# 01-PCIe.net
KiCad netlist of a schematic drawn in Altium Designer
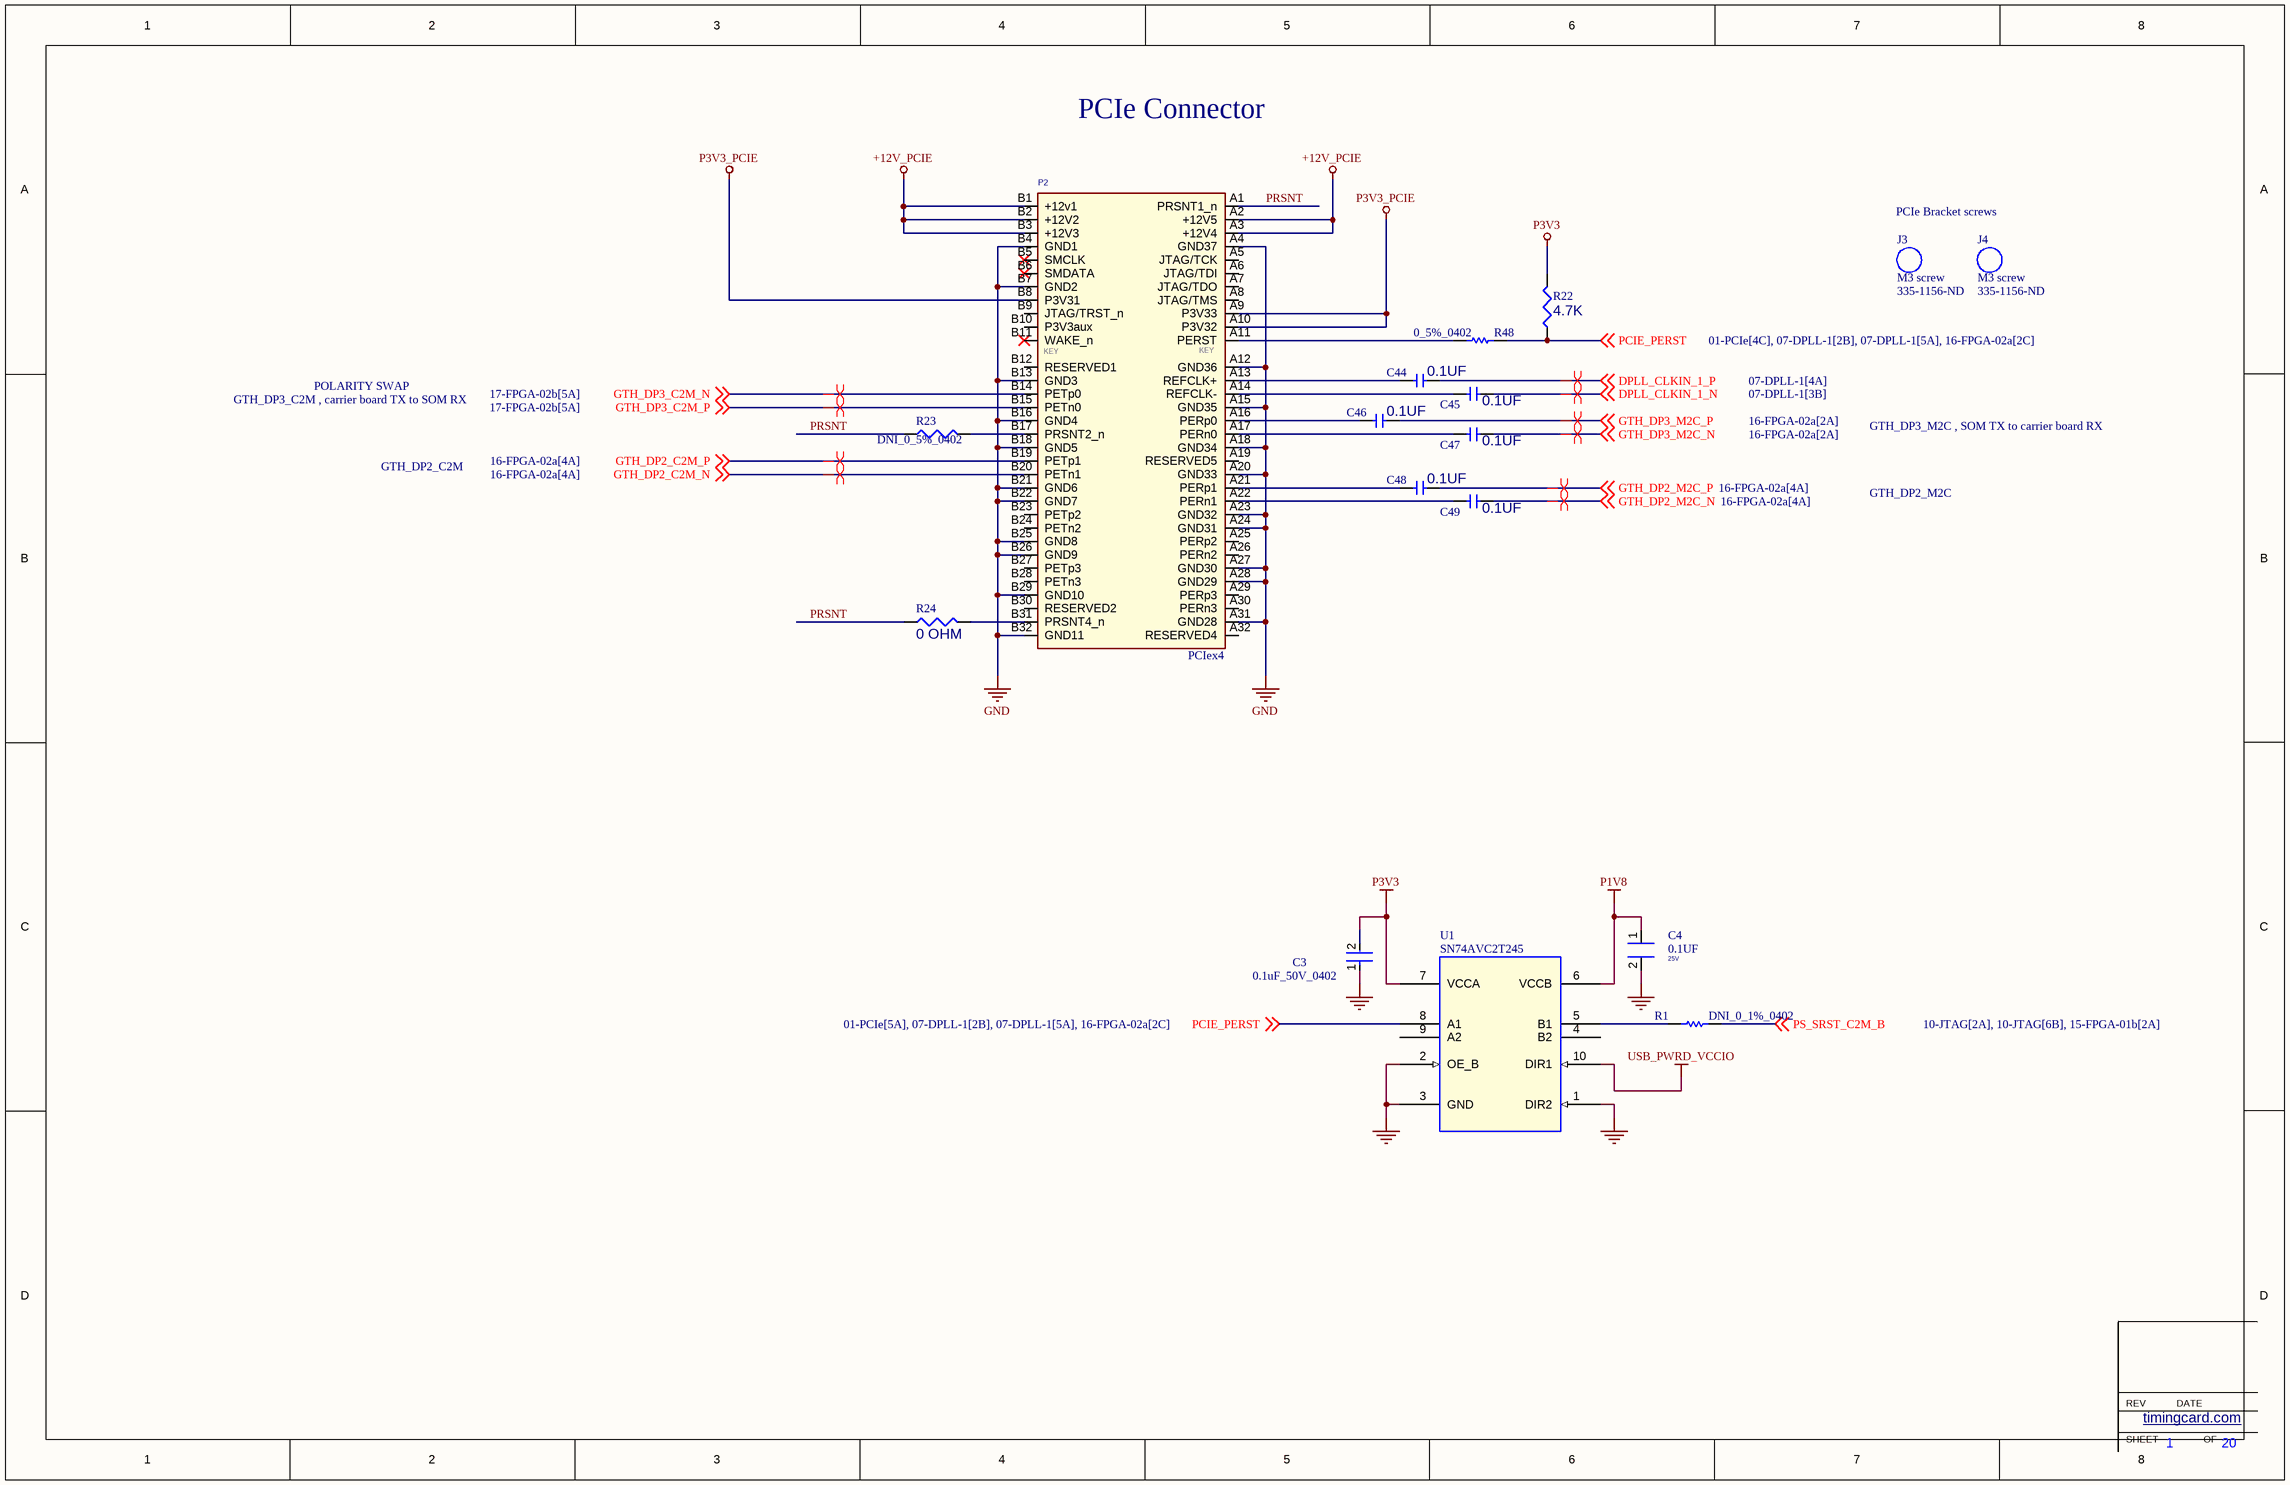
[diagram p0: 01-PCIe.SchDoc]

(export (version "E")
  (design (tool "Eeschema 10.0.6"))
  (components
    (comp (ref "C3")
      (value "0.1uF_50V_0402")
      (footprint "FP-C1005-050-0_05-IPC_C")
      (description "Multilayer Ceramic Capacitors 100nF ±10% 50V X7R SMD 0402")
      (fields (field (name "VOLTAGE") "50V") (field (name "TOLERANCE") "10%"))
      (libsource (lib "Altium Content Vault") (part "b4654b650e69147ec39a6b967a45e02"))
    )
    (comp (ref "C4")
      (value "0.1UF")
      (footprint "CAPC100X50X55")
      (description "Cap Cer 100nF 10% 25V X5R 0402")
      (fields
        (field (name "VOLTAGE") "25V")
        (field (name "MANUFACTURER") "TAIYO YUDEN")
        (field (name "AGILE PART NUMBER") "CAP-00068-01")
        (field (name "OWNER") "4001")
      )
      (libsource (lib "*") (part "CAP_NP"))
    )
    (comp (ref "C44")
      (value "0.1UF")
      (footprint "CAPC1005X06N")
      (description "CAP, CER, 0.1UF, 50V, 10%, X7R, AEC-Q200, 0402")
      (fields
        (field (name "MFG PART NUM") "CGA2B3X7R1H104K050BB")
        (field (name "VALENTIUM PART NUM") "<VALENTIUM>")
      )
      (libsource (lib "Capacitors") (part "CAP_0402_0.1UF_50V"))
    )
    (comp (ref "C45")
      (value "0.1UF")
      (footprint "CAPC1005X06N")
      (description "CAP, CER, 0.1UF, 50V, 10%, X7R, AEC-Q200, 0402")
      (fields
        (field (name "MFG PART NUM") "CGA2B3X7R1H104K050BB")
        (field (name "VALENTIUM PART NUM") "<VALENTIUM>")
      )
      (libsource (lib "Capacitors") (part "CAP_0402_0.1UF_50V"))
    )
    (comp (ref "C46")
      (value "0.1UF")
      (footprint "CAPC1005X06N")
      (description "CAP, CER, 0.1UF, 50V, 10%, X7R, AEC-Q200, 0402")
      (fields
        (field (name "MFG PART NUM") "CGA2B3X7R1H104K050BB")
        (field (name "VALENTIUM PART NUM") "<VALENTIUM>")
      )
      (libsource (lib "Capacitors") (part "CAP_0402_0.1UF_50V"))
    )
    (comp (ref "C47")
      (value "0.1UF")
      (footprint "CAPC1005X06N")
      (description "CAP, CER, 0.1UF, 50V, 10%, X7R, AEC-Q200, 0402")
      (fields
        (field (name "MFG PART NUM") "CGA2B3X7R1H104K050BB")
        (field (name "VALENTIUM PART NUM") "<VALENTIUM>")
      )
      (libsource (lib "Capacitors") (part "CAP_0402_0.1UF_50V"))
    )
    (comp (ref "C48")
      (value "0.1UF")
      (footprint "CAPC1005X06N")
      (description "CAP, CER, 0.1UF, 50V, 10%, X7R, AEC-Q200, 0402")
      (fields
        (field (name "MFG PART NUM") "CGA2B3X7R1H104K050BB")
        (field (name "VALENTIUM PART NUM") "<VALENTIUM>")
      )
      (libsource (lib "Capacitors") (part "CAP_0402_0.1UF_50V"))
    )
    (comp (ref "C49")
      (value "0.1UF")
      (footprint "CAPC1005X06N")
      (description "CAP, CER, 0.1UF, 50V, 10%, X7R, AEC-Q200, 0402")
      (fields
        (field (name "MFG PART NUM") "CGA2B3X7R1H104K050BB")
        (field (name "VALENTIUM PART NUM") "<VALENTIUM>")
      )
      (libsource (lib "Capacitors") (part "CAP_0402_0.1UF_50V"))
    )
    (comp (ref "J3")
      (value "M3 screw")
      (fields (field (name "SUPPLIER PART NUMBER 1") "335-1156-ND"))
      (libsource (lib "FPGA_CONN") (part "M3 screw"))
    )
    (comp (ref "J4")
      (value "M3 screw")
      (fields (field (name "SUPPLIER PART NUMBER 1") "335-1156-ND"))
      (libsource (lib "FPGA_CONN") (part "M3 screw"))
    )
    (comp (ref "P2")
      (value "PCIex4")
      (footprint "PCIE_4LANE_EDGE")
      (description "PCIE x4 Edge Connector,OrCAD Symbol,NC")
      (fields (field (name "PART NUMBER") "451") (field (name "MANUFACTURER") "NA"))
      (libsource (lib "Connectors") (part "PCIex4"))
    )
    (comp (ref "R1")
      (value "DNI_0_1%_0402")
      (footprint "RESC1005X40X25LL05T05")
      (description "Chip Resistor, 0 Ohm, 0.1 W, -55 to 155 degC, 0402 (1005 Metric), RoHS, Tape and Reel")
      (fields (field (name "MANUFACTURER") "Panasonic") (field (name "TOLERANCE") "5%"))
      (libsource (lib "Altium Content Vault") (part "RES-2"))
    )
    (comp (ref "R22")
      (value "4.7K")
      (footprint "RESC1608X50N")
      (description "RES, 4.7K, 1%, 1/10W, TF, 0603")
      (fields (field (name "MFG PART NUM") "ERJ-3EKF4701V") (field (name "VELENTIUM PART NUM") "<VELENTIUM>"))
      (libsource (lib "Resistors") (part "RES_0603_4.7K"))
    )
    (comp (ref "R23")
      (value "DNI_0_5%_0402")
      (footprint "RESC1005X04N")
      (description "RES, 0. OHM, 1%, 1/16W, TF, AEC-Q200, 0402")
      (fields (field (name "MFG PART NUM") "ERJ-2GE0R00X") (field (name "VELENTIUM PART NUM") "<VELENTIUM>"))
      (libsource (lib "Resistors") (part "RES_0402_0"))
    )
    (comp (ref "R24")
      (value "0 OHM")
      (footprint "RESC1005X04N")
      (description "RES, 0. OHM, 1%, 1/16W, TF, AEC-Q200, 0402")
      (fields (field (name "MFG PART NUM") "ERJ-2GE0R00X") (field (name "VELENTIUM PART NUM") "<VELENTIUM>"))
      (libsource (lib "Resistors") (part "RES_0402_0"))
    )
    (comp (ref "R48")
      (value "0_5%_0402")
      (footprint "RESC1005X40X25LL10T10")
      (fields (field (name "MANUFACTURER") "KOA Speer") (field (name "PART NUMBER") "RK73Z1ETTP"))
      (libsource (lib "Altium Content Vault") (part "RES"))
    )
    (comp (ref "U1")
      (value "SN74AVC2T245")
      (footprint "QFN40P140X180X55-10")
      (description "IC Lvl Trans 2-Bit Bidir 500Mbps 1.2-3.6V 50mA UQFN-10")
      (fields
        (field (name "MANUFACTURER") "TEXAS INSTRUMENTS")
        (field (name "AGILE PART NUMBER") "ICS-00048-01")
      )
      (libsource (lib "*") (part "SN74AVC2T245"))
    )
  )
  (nets
    (net (code "1") (name "+12V_PCIE") (class "Default")
      (node (ref "P2") (pin "A2") (pinfunction "+12V5_A2") (pintype "passive"))
      (node (ref "P2") (pin "A3") (pinfunction "+12V4_A3") (pintype "passive"))
      (node (ref "P2") (pin "B1") (pinfunction "+12v1_B1") (pintype "power_in"))
      (node (ref "P2") (pin "B2") (pinfunction "+12V2_B2") (pintype "power_in"))
      (node (ref "P2") (pin "B3") (pinfunction "+12V3_B3") (pintype "power_in"))
    )
    (net (code "2") (name "/PRSNT") (class "Default")
      (node (ref "P2") (pin "A1") (pinfunction "PRSNT1_n_A1") (pintype "passive"))
      (node (ref "R23") (pin "1") (pinfunction "1_1") (pintype "passive"))
      (node (ref "R24") (pin "1") (pinfunction "1_1") (pintype "passive"))
    )
    (net (code "3") (name "DPLL_CLKIN_1_N") (class "Default")
      (node (ref "C45") (pin "2") (pinfunction "2_2") (pintype "passive"))
    )
    (net (code "4") (name "DPLL_CLKIN_1_P") (class "Default")
      (node (ref "C44") (pin "2") (pinfunction "2_2") (pintype "passive"))
    )
    (net (code "5") (name "GND") (class "Default")
      (node (ref "C3") (pin "1") (pinfunction "1_1") (pintype "passive"))
      (node (ref "C4") (pin "2") (pinfunction "2_2") (pintype "passive"))
      (node (ref "P2") (pin "A12") (pinfunction "GND36_A12") (pintype "power_in"))
      (node (ref "P2") (pin "A15") (pinfunction "GND35_A15") (pintype "power_in"))
      (node (ref "P2") (pin "A18") (pinfunction "GND34_A18") (pintype "power_in"))
      (node (ref "P2") (pin "A20") (pinfunction "GND33_A20") (pintype "power_in"))
      (node (ref "P2") (pin "A23") (pinfunction "GND32_A23") (pintype "power_in"))
      (node (ref "P2") (pin "A24") (pinfunction "GND31_A24") (pintype "power_in"))
      (node (ref "P2") (pin "A27") (pinfunction "GND30_A27") (pintype "power_in"))
      (node (ref "P2") (pin "A28") (pinfunction "GND29_A28") (pintype "power_in"))
      (node (ref "P2") (pin "A31") (pinfunction "GND28_A31") (pintype "power_in"))
      (node (ref "P2") (pin "A4") (pinfunction "GND37_A4") (pintype "power_in"))
      (node (ref "P2") (pin "B13") (pinfunction "GND3_B13") (pintype "power_in"))
      (node (ref "P2") (pin "B16") (pinfunction "GND4_B16") (pintype "power_in"))
      (node (ref "P2") (pin "B18") (pinfunction "GND5_B18") (pintype "power_in"))
      (node (ref "P2") (pin "B21") (pinfunction "GND6_B21") (pintype "power_in"))
      (node (ref "P2") (pin "B22") (pinfunction "GND7_B22") (pintype "power_in"))
      (node (ref "P2") (pin "B25") (pinfunction "GND8_B25") (pintype "power_in"))
      (node (ref "P2") (pin "B26") (pinfunction "GND9_B26") (pintype "power_in"))
      (node (ref "P2") (pin "B29") (pinfunction "GND10_B29") (pintype "power_in"))
      (node (ref "P2") (pin "B32") (pinfunction "GND11_B32") (pintype "power_in"))
      (node (ref "P2") (pin "B4") (pinfunction "GND1_B4") (pintype "power_in"))
      (node (ref "P2") (pin "B7") (pinfunction "GND2_B7") (pintype "power_in"))
      (node (ref "U1") (pin "1") (pinfunction "DIR2_1") (pintype "input"))
      (node (ref "U1") (pin "2") (pinfunction "OE_B_2") (pintype "input"))
      (node (ref "U1") (pin "3") (pinfunction "GND_3") (pintype "power_in"))
    )
    (net (code "6") (name "GTH_DP2_C2M_N") (class "Default")
      (node (ref "P2") (pin "B20") (pinfunction "PETn1_B20") (pintype "passive"))
    )
    (net (code "7") (name "GTH_DP2_C2M_P") (class "Default")
      (node (ref "P2") (pin "B19") (pinfunction "PETp1_B19") (pintype "passive"))
    )
    (net (code "8") (name "GTH_DP2_M2C_N") (class "Default")
      (node (ref "C49") (pin "2") (pinfunction "2_2") (pintype "passive"))
    )
    (net (code "9") (name "GTH_DP2_M2C_P") (class "Default")
      (node (ref "C48") (pin "2") (pinfunction "2_2") (pintype "passive"))
    )
    (net (code "10") (name "GTH_DP3_C2M_N") (class "Default")
      (node (ref "P2") (pin "B14") (pinfunction "PETp0_B14") (pintype "passive"))
    )
    (net (code "11") (name "GTH_DP3_C2M_P") (class "Default")
      (node (ref "P2") (pin "B15") (pinfunction "PETn0_B15") (pintype "passive"))
    )
    (net (code "12") (name "GTH_DP3_M2C_N") (class "Default")
      (node (ref "C47") (pin "2") (pinfunction "2_2") (pintype "passive"))
    )
    (net (code "13") (name "GTH_DP3_M2C_P") (class "Default")
      (node (ref "C46") (pin "2") (pinfunction "2_2") (pintype "passive"))
    )
    (net (code "14") (name "Net-(P2-PERST)") (class "Default")
      (node (ref "P2") (pin "A11") (pinfunction "PERST_A11") (pintype "passive"))
      (node (ref "R48") (pin "1") (pinfunction "1_1") (pintype "passive"))
    )
    (net (code "15") (name "Net-(P2-PERn0)") (class "Default")
      (node (ref "C47") (pin "1") (pinfunction "1_1") (pintype "passive"))
      (node (ref "P2") (pin "A17") (pinfunction "PERn0_A17") (pintype "passive"))
    )
    (net (code "16") (name "Net-(P2-PERn1)") (class "Default")
      (node (ref "C49") (pin "1") (pinfunction "1_1") (pintype "passive"))
      (node (ref "P2") (pin "A22") (pinfunction "PERn1_A22") (pintype "passive"))
    )
    (net (code "17") (name "Net-(P2-PERp0)") (class "Default")
      (node (ref "C46") (pin "1") (pinfunction "1_1") (pintype "passive"))
      (node (ref "P2") (pin "A16") (pinfunction "PERp0_A16") (pintype "passive"))
    )
    (net (code "18") (name "Net-(P2-PERp1)") (class "Default")
      (node (ref "C48") (pin "1") (pinfunction "1_1") (pintype "passive"))
      (node (ref "P2") (pin "A21") (pinfunction "PERp1_A21") (pintype "passive"))
    )
    (net (code "19") (name "Net-(P2-PRSNT2_n)") (class "Default")
      (node (ref "P2") (pin "B17") (pinfunction "PRSNT2_n_B17") (pintype "passive"))
      (node (ref "R23") (pin "2") (pinfunction "2_2") (pintype "passive"))
    )
    (net (code "20") (name "Net-(P2-PRSNT4_n)") (class "Default")
      (node (ref "P2") (pin "B31") (pinfunction "PRSNT4_n_B31") (pintype "passive"))
      (node (ref "R24") (pin "2") (pinfunction "2_2") (pintype "passive"))
    )
    (net (code "21") (name "Net-(P2-REFCLK+)") (class "Default")
      (node (ref "C44") (pin "1") (pinfunction "1_1") (pintype "passive"))
      (node (ref "P2") (pin "A13") (pinfunction "REFCLK+_A13") (pintype "passive"))
    )
    (net (code "22") (name "Net-(P2-REFCLK-)") (class "Default")
      (node (ref "C45") (pin "1") (pinfunction "1_1") (pintype "passive"))
      (node (ref "P2") (pin "A14") (pinfunction "REFCLK-_A14") (pintype "passive"))
    )
    (net (code "23") (name "Net-(U1-B1)") (class "Default")
      (node (ref "R1") (pin "1") (pinfunction "1_1") (pintype "passive"))
      (node (ref "U1") (pin "5") (pinfunction "B1_5") (pintype "passive"))
    )
    (net (code "24") (name "P1V8") (class "Default")
      (node (ref "C4") (pin "1") (pinfunction "1_1") (pintype "passive"))
      (node (ref "U1") (pin "6") (pinfunction "VCCB_6") (pintype "power_in"))
    )
    (net (code "25") (name "P3V3") (class "Default")
      (node (ref "C3") (pin "2") (pinfunction "2_2") (pintype "passive"))
      (node (ref "R22") (pin "2") (pinfunction "2_2") (pintype "passive"))
      (node (ref "U1") (pin "7") (pinfunction "VCCA_7") (pintype "power_in"))
    )
    (net (code "26") (name "P3V3_PCIE") (class "Default")
      (node (ref "P2") (pin "A10") (pinfunction "P3V32_A10") (pintype "passive"))
      (node (ref "P2") (pin "A9") (pinfunction "P3V33_A9") (pintype "passive"))
      (node (ref "P2") (pin "B8") (pinfunction "P3V31_B8") (pintype "power_in"))
    )
    (net (code "27") (name "PCIE_PERST") (class "Default")
      (node (ref "R22") (pin "1") (pinfunction "1_1") (pintype "passive"))
      (node (ref "R48") (pin "2") (pinfunction "2_2") (pintype "passive"))
      (node (ref "U1") (pin "8") (pinfunction "A1_8") (pintype "passive"))
    )
    (net (code "28") (name "PS_SRST_C2M_B") (class "Default")
      (node (ref "R1") (pin "2") (pinfunction "2_2") (pintype "passive"))
    )
    (net (code "29") (name "USB_PWRD_VCCIO") (class "Default")
      (node (ref "U1") (pin "10") (pinfunction "DIR1_10") (pintype "input"))
    )
    (net (code "30") (name "unconnected-(P2-JTAG{slash}TCK-PadA5)") (class "Default")
      (node (ref "P2") (pin "A5") (pinfunction "JTAG/TCK_A5") (pintype "passive"))
    )
    (net (code "31") (name "unconnected-(P2-JTAG{slash}TDI-PadA6)") (class "Default")
      (node (ref "P2") (pin "A6") (pinfunction "JTAG/TDI_A6") (pintype "passive"))
    )
    (net (code "32") (name "unconnected-(P2-JTAG{slash}TDO-PadA7)") (class "Default")
      (node (ref "P2") (pin "A7") (pinfunction "JTAG/TDO_A7") (pintype "passive"))
    )
    (net (code "33") (name "unconnected-(P2-JTAG{slash}TMS-PadA8)") (class "Default")
      (node (ref "P2") (pin "A8") (pinfunction "JTAG/TMS_A8") (pintype "passive"))
    )
    (net (code "34") (name "unconnected-(P2-JTAG{slash}TRST_n-PadB9)") (class "Default")
      (node (ref "P2") (pin "B9") (pinfunction "JTAG/TRST_n_B9") (pintype "passive"))
    )
    (net (code "35") (name "unconnected-(P2-P3V3aux-PadB10)") (class "Default")
      (node (ref "P2") (pin "B10") (pinfunction "P3V3aux_B10") (pintype "passive"))
    )
    (net (code "36") (name "unconnected-(P2-PERn2-PadA26)") (class "Default")
      (node (ref "P2") (pin "A26") (pinfunction "PERn2_A26") (pintype "passive"))
    )
    (net (code "37") (name "unconnected-(P2-PERn3-PadA30)") (class "Default")
      (node (ref "P2") (pin "A30") (pinfunction "PERn3_A30") (pintype "passive"))
    )
    (net (code "38") (name "unconnected-(P2-PERp2-PadA25)") (class "Default")
      (node (ref "P2") (pin "A25") (pinfunction "PERp2_A25") (pintype "passive"))
    )
    (net (code "39") (name "unconnected-(P2-PERp3-PadA29)") (class "Default")
      (node (ref "P2") (pin "A29") (pinfunction "PERp3_A29") (pintype "passive"))
    )
    (net (code "40") (name "unconnected-(P2-PETn2-PadB24)") (class "Default")
      (node (ref "P2") (pin "B24") (pinfunction "PETn2_B24") (pintype "passive"))
    )
    (net (code "41") (name "unconnected-(P2-PETn3-PadB28)") (class "Default")
      (node (ref "P2") (pin "B28") (pinfunction "PETn3_B28") (pintype "passive"))
    )
    (net (code "42") (name "unconnected-(P2-PETp2-PadB23)") (class "Default")
      (node (ref "P2") (pin "B23") (pinfunction "PETp2_B23") (pintype "passive"))
    )
    (net (code "43") (name "unconnected-(P2-PETp3-PadB27)") (class "Default")
      (node (ref "P2") (pin "B27") (pinfunction "PETp3_B27") (pintype "passive"))
    )
    (net (code "44") (name "unconnected-(P2-RESERVED1-PadB12)") (class "Default")
      (node (ref "P2") (pin "B12") (pinfunction "RESERVED1_B12") (pintype "passive"))
    )
    (net (code "45") (name "unconnected-(P2-RESERVED2-PadB30)") (class "Default")
      (node (ref "P2") (pin "B30") (pinfunction "RESERVED2_B30") (pintype "passive"))
    )
    (net (code "46") (name "unconnected-(P2-RESERVED4-PadA32)") (class "Default")
      (node (ref "P2") (pin "A32") (pinfunction "RESERVED4_A32") (pintype "passive"))
    )
    (net (code "47") (name "unconnected-(P2-RESERVED5-PadA19)") (class "Default")
      (node (ref "P2") (pin "A19") (pinfunction "RESERVED5_A19") (pintype "passive"))
    )
    (net (code "48") (name "unconnected-(P2-SMCLK-PadB5)") (class "Default")
      (node (ref "P2") (pin "B5") (pinfunction "SMCLK_B5") (pintype "passive+no_connect"))
    )
    (net (code "49") (name "unconnected-(P2-SMDATA-PadB6)") (class "Default")
      (node (ref "P2") (pin "B6") (pinfunction "SMDATA_B6") (pintype "passive+no_connect"))
    )
    (net (code "50") (name "unconnected-(P2-WAKE_n-PadB11)") (class "Default")
      (node (ref "P2") (pin "B11") (pinfunction "WAKE_n_B11") (pintype "passive+no_connect"))
    )
    (net (code "51") (name "unconnected-(U1-A2-Pad9)") (class "Default")
      (node (ref "U1") (pin "9") (pinfunction "A2_9") (pintype "passive"))
    )
    (net (code "52") (name "unconnected-(U1-B2-Pad4)") (class "Default")
      (node (ref "U1") (pin "4") (pinfunction "B2_4") (pintype "passive"))
    )
  )
)
